# 07_EL_CON.net
KiCad netlist of a schematic drawn in Altium Designer
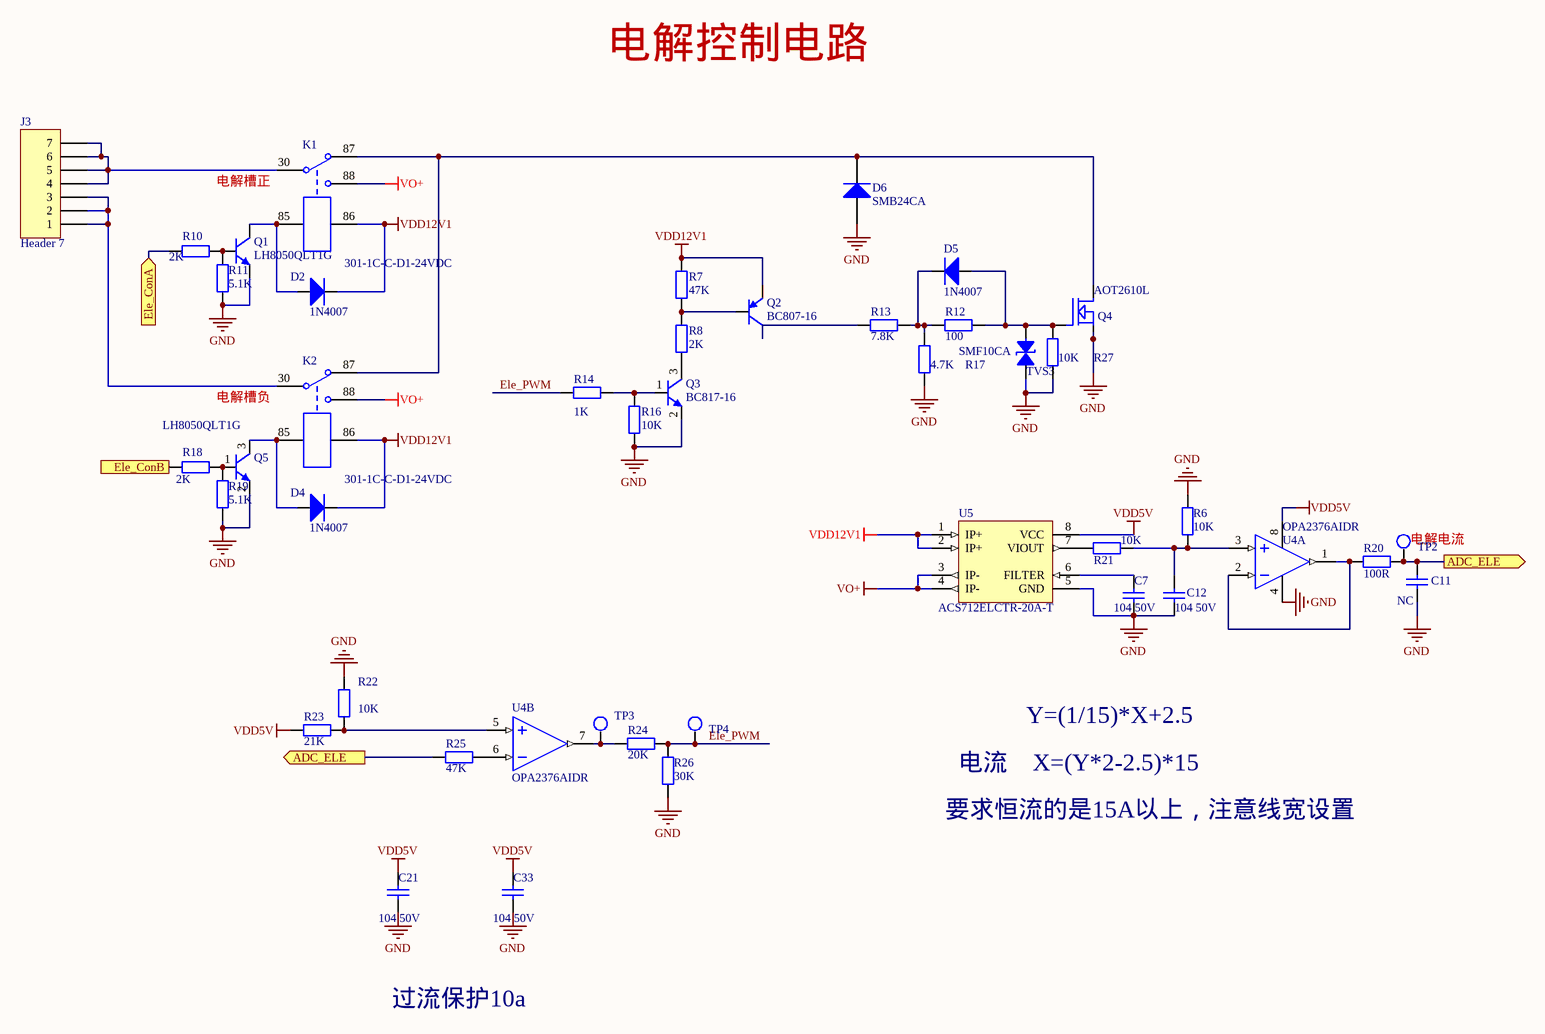
[diagram p0: 07_EL_CON.SchDoc]

(export (version "E")
  (design (tool "Eeschema 10.0.6"))
  (components
    (comp (ref "C7")
      (value "104 50V")
      (footprint "SMD-0603C")
      (description "贴片电容 10%")
      (libsource (lib "XiaoyI") (part "CAP4"))
    )
    (comp (ref "C11")
      (value "NC")
      (footprint "SMD-0603C")
      (description "贴片电容 10%")
      (libsource (lib "XiaoyI") (part "CAP4"))
    )
    (comp (ref "C12")
      (value "104 50V")
      (footprint "SMD-0603C")
      (description "贴片电容 10%")
      (libsource (lib "XiaoyI") (part "CAP4"))
    )
    (comp (ref "C21")
      (value "104 50V")
      (footprint "SMD-0603C")
      (description "贴片电容 20%")
      (libsource (lib "XiaoyI") (part "CAP4"))
    )
    (comp (ref "C33")
      (value "104 50V")
      (footprint "SMD-0603C")
      (description "贴片电容 20%")
      (libsource (lib "XiaoyI") (part "CAP4"))
    )
    (comp (ref "D2")
      (value "1N4007")
      (footprint "DO-214-AC")
      (description "贴片二极管")
      (libsource (lib "XiaoyI") (part "DIODE2"))
    )
    (comp (ref "D4")
      (value "1N4007")
      (footprint "DO-214-AC")
      (description "贴片二极管")
      (libsource (lib "XiaoyI") (part "DIODE2"))
    )
    (comp (ref "D5")
      (value "1N4007")
      (footprint "DO-214-AC")
      (description "贴片二极管")
      (libsource (lib "XiaoyI") (part "DIODE2"))
    )
    (comp (ref "D6")
      (value "SMB24CA")
      (footprint "Pcblib_20110825:SMB")
      (libsource (lib "Sch_library") (part "DIODE"))
    )
    (comp (ref "J3")
      (value "Header 7")
      (footprint "VH-AW-3.96*7P")
      (description "Header, 7-Pin")
      (fields (field (name "PUBLISHER") "Altium Limited"))
      (libsource (lib "Miscellaneous Connectors") (part "Header 7"))
    )
    (comp (ref "K1")
      (value "301-1C-C-D1-24VDC")
      (footprint "PCB1:301-1C-C-R1-24VDC")
      (description "5V 继电器")
      (libsource (lib "XiaoyI") (part "JDQ1"))
    )
    (comp (ref "K2")
      (value "301-1C-C-D1-24VDC")
      (footprint "PCB1:301-1C-C-R1-24VDC")
      (description "5V 继电器")
      (libsource (lib "XiaoyI") (part "JDQ1"))
    )
    (comp (ref "Q1")
      (value "LH8050QLT1G")
      (footprint "SOT-23")
      (description "三极管")
      (libsource (lib "XiaoyI") (part "NPN-1"))
    )
    (comp (ref "Q2")
      (value "BC807-16")
      (footprint "SOT-23")
      (description "PNP")
      (libsource (lib "XiaoyI") (part "PNP"))
    )
    (comp (ref "Q3")
      (value "BC817-16")
      (footprint "SOT-23")
      (description "三极管")
      (libsource (lib "") (part "NPN-1_1"))
    )
    (comp (ref "Q4")
      (value "AOT2610L")
      (footprint "Pcblib_20110825:to220")
      (libsource (lib "POWER") (part "SI7860"))
    )
    (comp (ref "Q5")
      (value "LH8050QLT1G")
      (footprint "SOT-23")
      (description "三极管")
      (libsource (lib "") (part "NPN-1_1"))
    )
    (comp (ref "R6")
      (value "10K")
      (footprint "SMD-0603")
      (description "贴片电阻 1%")
      (libsource (lib "") (part "RES0_1"))
    )
    (comp (ref "R7")
      (value "47K")
      (footprint "SMD-0603")
      (description "贴片电阻 5%")
      (libsource (lib "") (part "RES-SOP_1"))
    )
    (comp (ref "R8")
      (value "2K")
      (footprint "SMD-0603")
      (description "贴片电阻 5%")
      (libsource (lib "") (part "RES-SOP_1"))
    )
    (comp (ref "R10")
      (value "2K")
      (footprint "SMD-0603")
      (description "贴片电阻 5%")
      (libsource (lib "") (part "RES2_1"))
    )
    (comp (ref "R11")
      (value "5.1K")
      (footprint "SMD-0603")
      (description "贴片电阻 5%")
      (libsource (lib "XiaoyI") (part "RES2"))
    )
    (comp (ref "R12")
      (value "100")
      (footprint "SMD-0603")
      (description "贴片电阻 5%")
      (libsource (lib "") (part "RES-SOP_2"))
    )
    (comp (ref "R13")
      (value "7.8K")
      (footprint "SMD-0603")
      (description "贴片电阻 5%")
      (libsource (lib "XiaoyI") (part "RES-SOP"))
    )
    (comp (ref "R14")
      (value "1K")
      (footprint "SMD-0603")
      (description "贴片电阻 5%")
      (libsource (lib "XiaoyI") (part "RES-SOP"))
    )
    (comp (ref "R16")
      (value "10K")
      (footprint "SMD-0603")
      (description "贴片电阻 5%")
      (libsource (lib "") (part "RES-SOP_1"))
    )
    (comp (ref "R17")
      (value "4.7K")
      (footprint "SMD-0603")
      (description "贴片电阻 5%")
      (libsource (lib "") (part "RES-SOP_3"))
    )
    (comp (ref "R18")
      (value "2K")
      (footprint "SMD-0603")
      (description "贴片电阻 5%")
      (libsource (lib "") (part "RES2_1"))
    )
    (comp (ref "R19")
      (value "5.1K")
      (footprint "SMD-0603")
      (description "贴片电阻 5%")
      (libsource (lib "XiaoyI") (part "RES2"))
    )
    (comp (ref "R20")
      (value "100R")
      (footprint "SMD-0603")
      (description "贴片电阻 5%")
      (libsource (lib "ABB") (part "RES0"))
    )
    (comp (ref "R21")
      (value "10K")
      (footprint "SMD-0603")
      (description "贴片电阻 1%")
      (libsource (lib "ABB") (part "RES0"))
    )
    (comp (ref "R22")
      (value "10K")
      (footprint "SMD-0603")
      (description "贴片电阻 5%")
      (libsource (lib "") (part "RES-SOP_1"))
    )
    (comp (ref "R23")
      (value "21K")
      (footprint "SMD-0603")
      (description "贴片电阻 5%")
      (libsource (lib "XiaoyI") (part "RES-SOP"))
    )
    (comp (ref "R24")
      (value "20K")
      (footprint "SMD-0603")
      (description "贴片电阻 5%")
      (libsource (lib "XiaoyI") (part "RES-SOP"))
    )
    (comp (ref "R25")
      (value "47K")
      (footprint "SMD-0603")
      (description "贴片电阻 5%")
      (libsource (lib "XiaoyI") (part "RES-SOP"))
    )
    (comp (ref "R26")
      (value "30K")
      (footprint "SMD-0603")
      (description "贴片电阻 5%")
      (libsource (lib "") (part "RES-SOP_3"))
    )
    (comp (ref "R27")
      (value "10K")
      (footprint "SMD-0603")
      (description "贴片电阻 5%")
      (libsource (lib "") (part "RES-SOP_3"))
    )
    (comp (ref "TP2") (value "TPS") (footprint "tpd") (libsource (lib "stm32") (part "TPS")))
    (comp (ref "TP3") (value "TPS") (footprint "tpd") (libsource (lib "stm32") (part "TPS")))
    (comp (ref "TP4") (value "TPS") (footprint "tpd") (libsource (lib "stm32") (part "TPS")))
    (comp (ref "TVS3")
      (value "SMF10CA")
      (footprint "SOD-123")
      (description "TVS 10V")
      (libsource (lib "XiaoyI") (part "TVS-1"))
    )
    (comp (ref "U4")
      (value "OPA2376AIDR")
      (footprint "SO-8")
      (description "运算放大器")
      (libsource (lib "XiaoyI") (part "LM358"))
    )
    (comp (ref "U5")
      (value "ACS712ELCTR-20A-T")
      (footprint "SO-8")
      (description "HALL 20A 电流传感器")
      (libsource (lib "XiaoyI") (part "ACS712"))
    )
  )
  (nets
    (net (code "1") (name "/ADC_ELE") (class "Default")
      (node (ref "C11") (pin "2") (pinfunction "2_2") (pintype "passive"))
      (node (ref "R20") (pin "1") (pinfunction "1_1") (pintype "passive"))
      (node (ref "R25") (pin "2") (pinfunction "2_2") (pintype "passive"))
      (node (ref "TP2") (pin "1") (pinfunction "1_1") (pintype "passive"))
    )
    (net (code "2") (name "/Ele_ConA") (class "Default")
      (node (ref "R10") (pin "1") (pinfunction "1_1") (pintype "passive"))
    )
    (net (code "3") (name "/Ele_ConB") (class "Default")
      (node (ref "R18") (pin "1") (pinfunction "1_1") (pintype "passive"))
    )
    (net (code "4") (name "/Ele_PWM") (class "Default")
      (node (ref "R14") (pin "2") (pinfunction "2_2") (pintype "passive"))
      (node (ref "R24") (pin "1") (pinfunction "1_1") (pintype "passive"))
      (node (ref "R26") (pin "1") (pinfunction "1_1") (pintype "passive"))
      (node (ref "TP4") (pin "1") (pinfunction "1_1") (pintype "passive"))
    )
    (net (code "5") (name "GND") (class "Default")
      (node (ref "C11") (pin "1") (pinfunction "1_1") (pintype "passive"))
      (node (ref "C12") (pin "2") (pinfunction "2_2") (pintype "passive"))
      (node (ref "C21") (pin "1") (pinfunction "1_1") (pintype "passive"))
      (node (ref "C33") (pin "1") (pinfunction "1_1") (pintype "passive"))
      (node (ref "C7") (pin "2") (pinfunction "2_2") (pintype "passive"))
      (node (ref "D6") (pin "1") (pinfunction "A_1") (pintype "passive"))
      (node (ref "Q1") (pin "2") (pinfunction "E_2") (pintype "passive"))
      (node (ref "Q3") (pin "2") (pinfunction "E_2") (pintype "passive"))
      (node (ref "Q4") (pin "3") (pinfunction "S_3") (pintype "passive"))
      (node (ref "Q5") (pin "2") (pinfunction "E_2") (pintype "passive"))
      (node (ref "R11") (pin "1") (pinfunction "1_1") (pintype "passive"))
      (node (ref "R16") (pin "1") (pinfunction "1_1") (pintype "passive"))
      (node (ref "R17") (pin "2") (pinfunction "2_2") (pintype "passive"))
      (node (ref "R19") (pin "1") (pinfunction "1_1") (pintype "passive"))
      (node (ref "R22") (pin "2") (pinfunction "2_2") (pintype "passive"))
      (node (ref "R26") (pin "2") (pinfunction "2_2") (pintype "passive"))
      (node (ref "R27") (pin "2") (pinfunction "2_2") (pintype "passive"))
      (node (ref "R6") (pin "1") (pinfunction "1_1") (pintype "passive"))
      (node (ref "TVS3") (pin "1") (pinfunction "A_1") (pintype "passive"))
      (node (ref "U4") (pin "4") (pinfunction "V-_4") (pintype "power_in"))
      (node (ref "U5") (pin "5") (pinfunction "GND_5") (pintype "power_in"))
    )
    (net (code "6") (name "Net-(D2-A)") (class "Default")
      (node (ref "D2") (pin "1") (pinfunction "A_1") (pintype "passive"))
      (node (ref "K1") (pin "85") (pinfunction "4_85") (pintype "passive"))
      (node (ref "Q1") (pin "3") (pinfunction "C_3") (pintype "passive"))
    )
    (net (code "7") (name "Net-(D4-A)") (class "Default")
      (node (ref "D4") (pin "1") (pinfunction "A_1") (pintype "passive"))
      (node (ref "K2") (pin "85") (pinfunction "4_85") (pintype "passive"))
      (node (ref "Q5") (pin "3") (pinfunction "C_3") (pintype "passive"))
    )
    (net (code "8") (name "Net-(D5-A)") (class "Default")
      (node (ref "D5") (pin "1") (pinfunction "A_1") (pintype "passive"))
      (node (ref "Q4") (pin "1") (pinfunction "G_1") (pintype "passive"))
      (node (ref "R12") (pin "2") (pinfunction "2_2") (pintype "passive"))
      (node (ref "R27") (pin "1") (pinfunction "1_1") (pintype "passive"))
      (node (ref "TVS3") (pin "2") (pinfunction "B_2") (pintype "passive"))
    )
    (net (code "9") (name "Net-(D5-K)") (class "Default")
      (node (ref "D5") (pin "2") (pinfunction "K_2") (pintype "passive"))
      (node (ref "R12") (pin "1") (pinfunction "1_1") (pintype "passive"))
      (node (ref "R13") (pin "1") (pinfunction "1_1") (pintype "passive"))
      (node (ref "R17") (pin "1") (pinfunction "1_1") (pintype "passive"))
    )
    (net (code "10") (name "Net-(D6-K)") (class "Default")
      (node (ref "D6") (pin "2") (pinfunction "K_2") (pintype "passive"))
      (node (ref "K1") (pin "87") (pinfunction "3_87") (pintype "passive"))
      (node (ref "K2") (pin "87") (pinfunction "3_87") (pintype "passive"))
      (node (ref "Q4") (pin "2") (pinfunction "D_2") (pintype "passive"))
    )
    (net (code "11") (name "Net-(K1-1)") (class "Default")
      (node (ref "J3") (pin "4") (pinfunction "4_4") (pintype "passive"))
      (node (ref "J3") (pin "5") (pinfunction "5_5") (pintype "passive"))
      (node (ref "J3") (pin "6") (pinfunction "6_6") (pintype "passive"))
      (node (ref "J3") (pin "7") (pinfunction "7_7") (pintype "passive"))
      (node (ref "K1") (pin "30") (pinfunction "1_30") (pintype "passive"))
    )
    (net (code "12") (name "Net-(K2-1)") (class "Default")
      (node (ref "J3") (pin "1") (pinfunction "1_1") (pintype "passive"))
      (node (ref "J3") (pin "2") (pinfunction "2_2") (pintype "passive"))
      (node (ref "J3") (pin "3") (pinfunction "3_3") (pintype "passive"))
      (node (ref "K2") (pin "30") (pinfunction "1_30") (pintype "passive"))
    )
    (net (code "13") (name "Net-(Q1-B)") (class "Default")
      (node (ref "Q1") (pin "1") (pinfunction "B_1") (pintype "passive"))
      (node (ref "R10") (pin "2") (pinfunction "2_2") (pintype "passive"))
      (node (ref "R11") (pin "2") (pinfunction "2_2") (pintype "passive"))
    )
    (net (code "14") (name "Net-(Q2-B)") (class "Default")
      (node (ref "Q2") (pin "1") (pinfunction "B_1") (pintype "passive"))
      (node (ref "R7") (pin "1") (pinfunction "1_1") (pintype "passive"))
      (node (ref "R8") (pin "2") (pinfunction "2_2") (pintype "passive"))
    )
    (net (code "15") (name "Net-(Q2-C)") (class "Default")
      (node (ref "Q2") (pin "3") (pinfunction "C_3") (pintype "passive"))
      (node (ref "R13") (pin "2") (pinfunction "2_2") (pintype "passive"))
    )
    (net (code "16") (name "Net-(Q3-B)") (class "Default")
      (node (ref "Q3") (pin "1") (pinfunction "B_1") (pintype "passive"))
      (node (ref "R14") (pin "1") (pinfunction "1_1") (pintype "passive"))
      (node (ref "R16") (pin "2") (pinfunction "2_2") (pintype "passive"))
    )
    (net (code "17") (name "Net-(Q3-C)") (class "Default")
      (node (ref "Q3") (pin "3") (pinfunction "C_3") (pintype "passive"))
      (node (ref "R8") (pin "1") (pinfunction "1_1") (pintype "passive"))
    )
    (net (code "18") (name "Net-(Q5-B)") (class "Default")
      (node (ref "Q5") (pin "1") (pinfunction "B_1") (pintype "passive"))
      (node (ref "R18") (pin "2") (pinfunction "2_2") (pintype "passive"))
      (node (ref "R19") (pin "2") (pinfunction "2_2") (pintype "passive"))
    )
    (net (code "19") (name "Net-(U4A-IN1+)") (class "Default")
      (node (ref "C12") (pin "1") (pinfunction "1_1") (pintype "passive"))
      (node (ref "R21") (pin "1") (pinfunction "1_1") (pintype "passive"))
      (node (ref "R6") (pin "2") (pinfunction "2_2") (pintype "passive"))
      (node (ref "U4") (pin "3") (pinfunction "IN1+_3") (pintype "input"))
    )
    (net (code "20") (name "Net-(U4A-IN1-)") (class "Default")
      (node (ref "R20") (pin "2") (pinfunction "2_2") (pintype "passive"))
      (node (ref "U4") (pin "1") (pinfunction "OUT1_1") (pintype "output"))
      (node (ref "U4") (pin "2") (pinfunction "IN1-_2") (pintype "input"))
    )
    (net (code "21") (name "Net-(U4B-IN2+)") (class "Default")
      (node (ref "R22") (pin "1") (pinfunction "1_1") (pintype "passive"))
      (node (ref "R23") (pin "1") (pinfunction "1_1") (pintype "passive"))
      (node (ref "U4") (pin "5") (pinfunction "IN2+_5") (pintype "input"))
    )
    (net (code "22") (name "Net-(U4B-IN2-)") (class "Default")
      (node (ref "R25") (pin "1") (pinfunction "1_1") (pintype "passive"))
      (node (ref "U4") (pin "6") (pinfunction "IN2-_6") (pintype "input"))
    )
    (net (code "23") (name "Net-(U4B-OUT2)") (class "Default")
      (node (ref "R24") (pin "2") (pinfunction "2_2") (pintype "passive"))
      (node (ref "TP3") (pin "1") (pinfunction "1_1") (pintype "passive"))
      (node (ref "U4") (pin "7") (pinfunction "OUT2_7") (pintype "output"))
    )
    (net (code "24") (name "Net-(U5-FILTER)") (class "Default")
      (node (ref "C7") (pin "1") (pinfunction "1_1") (pintype "passive"))
      (node (ref "U5") (pin "6") (pinfunction "FILTER_6") (pintype "input"))
    )
    (net (code "25") (name "Net-(U5-VIOUT)") (class "Default")
      (node (ref "R21") (pin "2") (pinfunction "2_2") (pintype "passive"))
      (node (ref "U5") (pin "7") (pinfunction "VIOUT_7") (pintype "output"))
    )
    (net (code "26") (name "VDD5V") (class "Default")
      (node (ref "C21") (pin "2") (pinfunction "2_2") (pintype "passive"))
      (node (ref "C33") (pin "2") (pinfunction "2_2") (pintype "passive"))
      (node (ref "R23") (pin "2") (pinfunction "2_2") (pintype "passive"))
      (node (ref "U4") (pin "8") (pinfunction "V+_8") (pintype "power_in"))
      (node (ref "U5") (pin "8") (pinfunction "VCC_8") (pintype "power_in"))
    )
    (net (code "27") (name "VDD12V1") (class "Default")
      (node (ref "D2") (pin "2") (pinfunction "K_2") (pintype "passive"))
      (node (ref "D4") (pin "2") (pinfunction "K_2") (pintype "passive"))
      (node (ref "K1") (pin "86") (pinfunction "5_86") (pintype "passive"))
      (node (ref "K2") (pin "86") (pinfunction "5_86") (pintype "passive"))
      (node (ref "Q2") (pin "2") (pinfunction "E_2") (pintype "passive"))
      (node (ref "R7") (pin "2") (pinfunction "2_2") (pintype "passive"))
      (node (ref "U5") (pin "1") (pinfunction "IP+_1") (pintype "input"))
      (node (ref "U5") (pin "2") (pinfunction "IP+_2") (pintype "input"))
    )
    (net (code "28") (name "VO+") (class "Default")
      (node (ref "K1") (pin "88") (pinfunction "2_88") (pintype "passive"))
      (node (ref "K2") (pin "88") (pinfunction "2_88") (pintype "passive"))
      (node (ref "U5") (pin "3") (pinfunction "IP-_3") (pintype "output"))
      (node (ref "U5") (pin "4") (pinfunction "IP-_4") (pintype "output"))
    )
  )
)
